# RadFET.net
KiCad netlist of a schematic drawn in Altium Designer
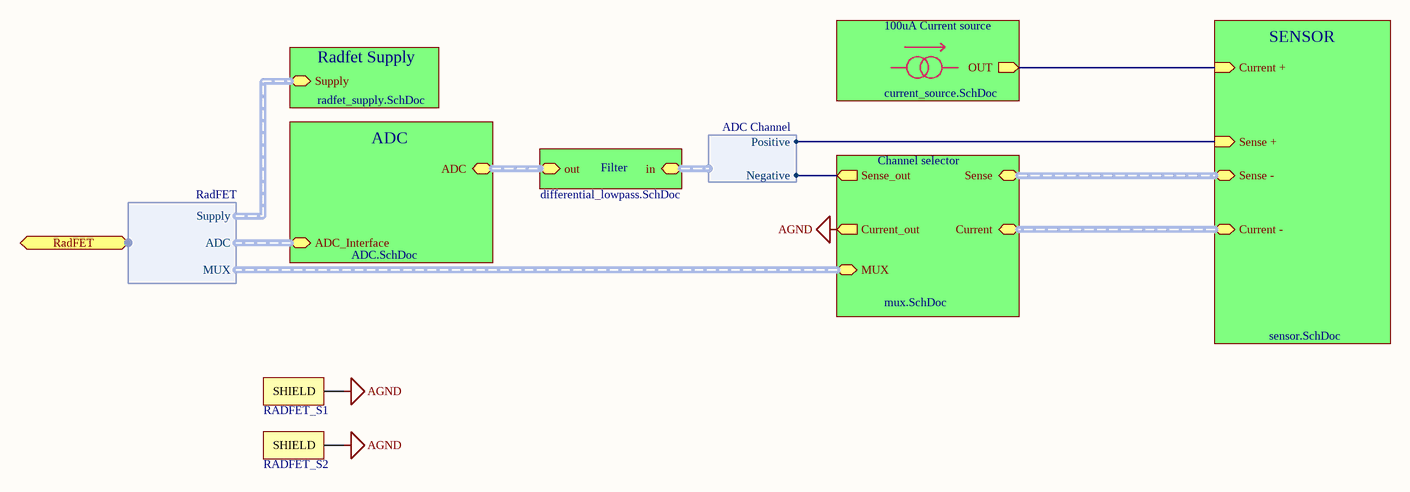
[diagram p0: RadFET.SchDoc]

(export (version "E")
  (design (tool "Eeschema 10.0.6"))
  (components
    (comp (ref "RADFET_S1")
      (value "BMI-S-203-F")
      (footprint "BMI-S-203-F_NO3D")
      (description "STANDARD SURFACE MOUNT SHIELD TWO-PIECE 26.21x26.21x5.08mm")
      (libsource (lib "rf") (part "BMI-S-203-F"))
    )
    (comp (ref "RADFET_S2")
      (value "BMI-S-203-F")
      (footprint "BMI-S-203-F_NO3D")
      (description "STANDARD SURFACE MOUNT SHIELD TWO-PIECE 26.21x26.21x5.08mm")
      (libsource (lib "rf") (part "BMI-S-203-F"))
    )
  )
  (nets
    (net (code "16") (name "AGND") (class "Default")
      (node (ref "RADFET_S1") (pin "0") (pinfunction "SHIELD_0") (pintype "passive"))
      (node (ref "RADFET_S2") (pin "0") (pinfunction "SHIELD_0") (pintype "passive"))
    )
  )
)
